# Power5VManagement.net
KiCad netlist of a schematic drawn in Altium Designer
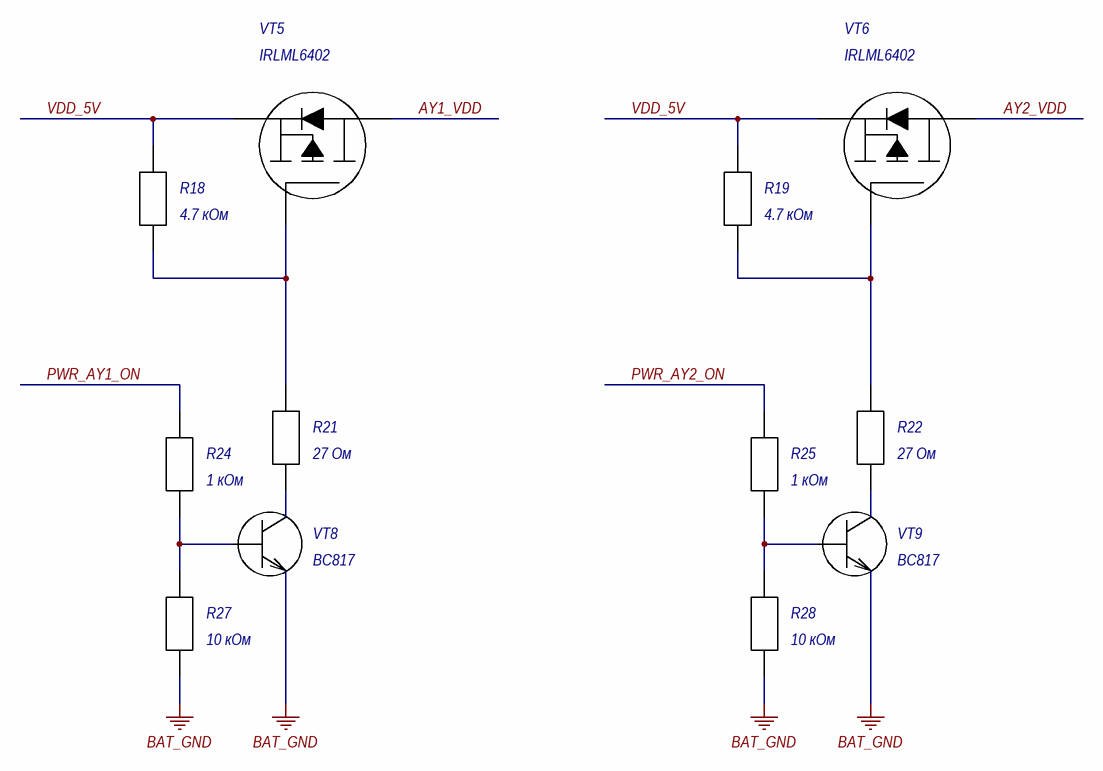
[diagram p0: Power5VManagement.SchDoc]

(export (version "E")
  (design (tool "Eeschema 10.0.6"))
  (components
    (comp (ref "R18") (value "4.7 кОм") (footprint "RES 0402") (libsource (lib "my_lib") (part "RES 0402")))
    (comp (ref "R19") (value "4.7 кОм") (footprint "RES 0402") (libsource (lib "my_lib") (part "RES 0402")))
    (comp (ref "R21") (value "27 Ом") (footprint "RES 0402") (libsource (lib "my_lib") (part "RES 0402")))
    (comp (ref "R22") (value "27 Ом") (footprint "RES 0402") (libsource (lib "my_lib") (part "RES 0402")))
    (comp (ref "R24") (value "1 кОм") (footprint "RES 0402") (libsource (lib "my_lib") (part "RES 0402")))
    (comp (ref "R25") (value "1 кОм") (footprint "RES 0402") (libsource (lib "my_lib") (part "RES 0402")))
    (comp (ref "R27") (value "10 кОм") (footprint "RES 0402") (libsource (lib "my_lib") (part "RES 0402")))
    (comp (ref "R28") (value "10 кОм") (footprint "RES 0402") (libsource (lib "my_lib") (part "RES 0402")))
    (comp (ref "VT5") (value "IRLML6402") (footprint "SOT-23") (libsource (lib "my_lib") (part "IRLML6402")))
    (comp (ref "VT6") (value "IRLML6402") (footprint "SOT-23") (libsource (lib "my_lib") (part "IRLML6402")))
    (comp (ref "VT8")
      (value "BC817")
      (footprint "SOT-23")
      (description "NPN general-purpose transistor")
      (fields (field (name "MANUFACTURER") "NXP"))
      (libsource (lib "my_lib") (part "BC817"))
    )
    (comp (ref "VT9")
      (value "BC817")
      (footprint "SOT-23")
      (description "NPN general-purpose transistor")
      (fields (field (name "MANUFACTURER") "NXP"))
      (libsource (lib "my_lib") (part "BC817"))
    )
  )
  (nets
    (net (code "1") (name "/AY1_VDD") (class "Default")
      (node (ref "VT5") (pin "3") (pinfunction "D_3") (pintype "passive"))
    )
    (net (code "2") (name "/AY2_VDD") (class "Default")
      (node (ref "VT6") (pin "3") (pinfunction "D_3") (pintype "passive"))
    )
    (net (code "3") (name "/PWR_AY1_ON") (class "Default")
      (node (ref "R24") (pin "2") (pinfunction "2_2") (pintype "passive"))
    )
    (net (code "4") (name "/PWR_AY2_ON") (class "Default")
      (node (ref "R25") (pin "2") (pinfunction "2_2") (pintype "passive"))
    )
    (net (code "5") (name "/VDD_5V") (class "Default")
      (node (ref "R18") (pin "2") (pinfunction "2_2") (pintype "passive"))
      (node (ref "R19") (pin "2") (pinfunction "2_2") (pintype "passive"))
      (node (ref "VT5") (pin "2") (pinfunction "S_2") (pintype "passive"))
      (node (ref "VT6") (pin "2") (pinfunction "S_2") (pintype "passive"))
    )
    (net (code "6") (name "BAT_GND") (class "Default")
      (node (ref "R27") (pin "1") (pinfunction "1_1") (pintype "passive"))
      (node (ref "R28") (pin "1") (pinfunction "1_1") (pintype "passive"))
      (node (ref "VT8") (pin "2") (pinfunction "E_2") (pintype "passive"))
      (node (ref "VT9") (pin "2") (pinfunction "E_2") (pintype "passive"))
    )
    (net (code "7") (name "Net-(VT5-G)") (class "Default")
      (node (ref "R18") (pin "1") (pinfunction "1_1") (pintype "passive"))
      (node (ref "R21") (pin "2") (pinfunction "2_2") (pintype "passive"))
      (node (ref "VT5") (pin "1") (pinfunction "G_1") (pintype "passive"))
    )
    (net (code "8") (name "Net-(VT6-G)") (class "Default")
      (node (ref "R19") (pin "1") (pinfunction "1_1") (pintype "passive"))
      (node (ref "R22") (pin "2") (pinfunction "2_2") (pintype "passive"))
      (node (ref "VT6") (pin "1") (pinfunction "G_1") (pintype "passive"))
    )
    (net (code "9") (name "Net-(VT8-B)") (class "Default")
      (node (ref "R24") (pin "1") (pinfunction "1_1") (pintype "passive"))
      (node (ref "R27") (pin "2") (pinfunction "2_2") (pintype "passive"))
      (node (ref "VT8") (pin "1") (pinfunction "B_1") (pintype "passive"))
    )
    (net (code "10") (name "Net-(VT8-C)") (class "Default")
      (node (ref "R21") (pin "1") (pinfunction "1_1") (pintype "passive"))
      (node (ref "VT8") (pin "3") (pinfunction "C_3") (pintype "passive"))
    )
    (net (code "11") (name "Net-(VT9-B)") (class "Default")
      (node (ref "R25") (pin "1") (pinfunction "1_1") (pintype "passive"))
      (node (ref "R28") (pin "2") (pinfunction "2_2") (pintype "passive"))
      (node (ref "VT9") (pin "1") (pinfunction "B_1") (pintype "passive"))
    )
    (net (code "12") (name "Net-(VT9-C)") (class "Default")
      (node (ref "R22") (pin "1") (pinfunction "1_1") (pintype "passive"))
      (node (ref "VT9") (pin "3") (pinfunction "C_3") (pintype "passive"))
    )
  )
)
